# Hub.net
KiCad netlist of a schematic drawn in EAGLE
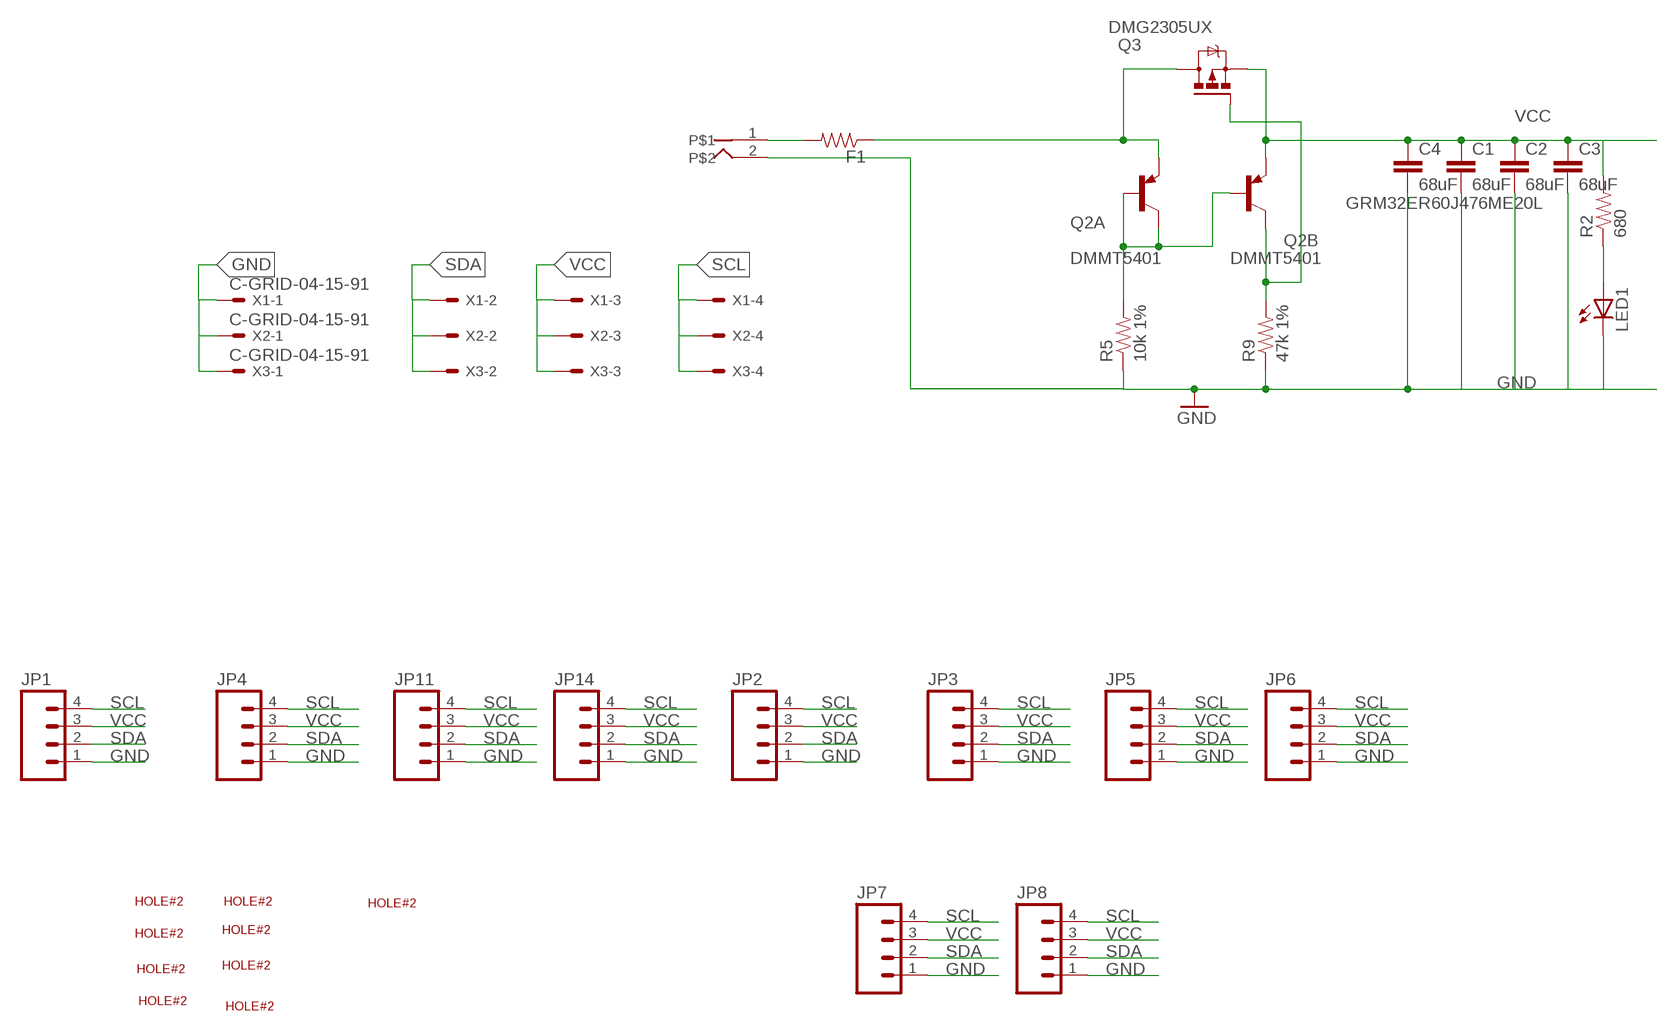
[diagram p0: schematic, sheet 1]

(export (version "E")
  (design (tool "Eeschema 10.0.6"))
  (components
    (comp (ref "C1")
      (value "68uF")
      (footprint "eagle-import:1210")
      (libsource (lib "eagle-import") (part "CAP1210"))
    )
    (comp (ref "C2")
      (value "68uF")
      (footprint "eagle-import:1210")
      (libsource (lib "eagle-import") (part "CAP1210"))
    )
    (comp (ref "C3")
      (value "68uF")
      (footprint "eagle-import:1210")
      (libsource (lib "eagle-import") (part "CAP1210"))
    )
    (comp (ref "C4")
      (value "68uF")
      (footprint "eagle-import:1210")
      (libsource (lib "eagle-import") (part "CAP1210"))
    )
    (comp (ref "F1")
      (value "RESISTOR0805-RES")
      (footprint "eagle-import:0805")
      (libsource (lib "eagle-import") (part "RESISTOR0805-RES"))
    )
    (comp (ref "JP1")
      (value "M04LOCK")
      (footprint "eagle-import:1X04_LOCK")
      (libsource (lib "eagle-import") (part "M04LOCK"))
    )
    (comp (ref "JP2")
      (value "M04LOCK")
      (footprint "eagle-import:1X04_LOCK")
      (libsource (lib "eagle-import") (part "M04LOCK"))
    )
    (comp (ref "JP3")
      (value "M04LOCK")
      (footprint "eagle-import:1X04_LOCK")
      (libsource (lib "eagle-import") (part "M04LOCK"))
    )
    (comp (ref "JP4")
      (value "M04LOCK")
      (footprint "eagle-import:1X04_LOCK")
      (libsource (lib "eagle-import") (part "M04LOCK"))
    )
    (comp (ref "JP5")
      (value "M04LOCK")
      (footprint "eagle-import:1X04_LOCK")
      (libsource (lib "eagle-import") (part "M04LOCK"))
    )
    (comp (ref "JP6")
      (value "M04LOCK")
      (footprint "eagle-import:1X04_LOCK")
      (libsource (lib "eagle-import") (part "M04LOCK"))
    )
    (comp (ref "JP7")
      (value "M04LOCK")
      (footprint "eagle-import:1X04_LOCK")
      (libsource (lib "eagle-import") (part "M04LOCK"))
    )
    (comp (ref "JP8")
      (value "M04LOCK")
      (footprint "eagle-import:1X04_LOCK")
      (libsource (lib "eagle-import") (part "M04LOCK"))
    )
    (comp (ref "JP11")
      (value "M04LOCK")
      (footprint "eagle-import:1X04_LOCK")
      (libsource (lib "eagle-import") (part "M04LOCK"))
    )
    (comp (ref "JP14")
      (value "M04LOCK")
      (footprint "eagle-import:1X04_LOCK")
      (libsource (lib "eagle-import") (part "M04LOCK"))
    )
    (comp (ref "LED1")
      (value "LEDCHIP-LED0805")
      (footprint "eagle-import:CHIP-LED0805")
      (libsource (lib "eagle-import") (part "LEDCHIP-LED0805"))
    )
    (comp (ref "Q2")
      (value "DMMT5401")
      (footprint "eagle-import:SOT-26")
      (libsource (lib "eagle-import") (part "TRANSISTOR-DUAL-PNP"))
    )
    (comp (ref "Q3")
      (value "DMG2305UX")
      (footprint "eagle-import:MICRO3")
      (libsource (lib "eagle-import") (part "IRLML5203"))
    )
    (comp (ref "R2")
      (value "680")
      (footprint "eagle-import:0805")
      (libsource (lib "eagle-import") (part "RESISTOR0805-RES"))
    )
    (comp (ref "R5")
      (value "10k 1%")
      (footprint "eagle-import:0805")
      (libsource (lib "eagle-import") (part "RESISTOR0805-RES"))
    )
    (comp (ref "R9")
      (value "47k 1%")
      (footprint "eagle-import:0805")
      (libsource (lib "eagle-import") (part "RESISTOR0805-RES"))
    )
    (comp (ref "U$1")
      (value "DC-JACKLOWPRO")
      (footprint "eagle-import:DC-POWER-JACK-LOWPRO")
      (libsource (lib "eagle-import") (part "DC-JACKLOWPRO"))
    )
    (comp (ref "U$6")
      (value "HOLE#2")
      (footprint "eagle-import:HOLE-#2")
      (libsource (lib "eagle-import") (part "HOLE#2"))
    )
    (comp (ref "U$7")
      (value "HOLE#2")
      (footprint "eagle-import:HOLE-#2")
      (libsource (lib "eagle-import") (part "HOLE#2"))
    )
    (comp (ref "U$8")
      (value "HOLE#2")
      (footprint "eagle-import:HOLE-#2")
      (libsource (lib "eagle-import") (part "HOLE#2"))
    )
    (comp (ref "U$9")
      (value "HOLE#2")
      (footprint "eagle-import:HOLE-#2")
      (libsource (lib "eagle-import") (part "HOLE#2"))
    )
    (comp (ref "U$10")
      (value "HOLE#2")
      (footprint "eagle-import:HOLE-#2")
      (libsource (lib "eagle-import") (part "HOLE#2"))
    )
    (comp (ref "U$11")
      (value "HOLE#2")
      (footprint "eagle-import:HOLE-#2")
      (libsource (lib "eagle-import") (part "HOLE#2"))
    )
    (comp (ref "U$12")
      (value "HOLE#2")
      (footprint "eagle-import:HOLE-#2")
      (libsource (lib "eagle-import") (part "HOLE#2"))
    )
    (comp (ref "U$13")
      (value "HOLE#2")
      (footprint "eagle-import:HOLE-#2")
      (libsource (lib "eagle-import") (part "HOLE#2"))
    )
    (comp (ref "U$14")
      (value "HOLE#2")
      (footprint "eagle-import:HOLE-#2")
      (libsource (lib "eagle-import") (part "HOLE#2"))
    )
    (comp (ref "X1")
      (value "C-GRID-04-15-91")
      (footprint "eagle-import:15-91-04")
      (libsource (lib "eagle-import") (part "C-GRID-04-15-91"))
    )
    (comp (ref "X2")
      (value "C-GRID-04-15-91")
      (footprint "eagle-import:15-91-04")
      (libsource (lib "eagle-import") (part "C-GRID-04-15-91"))
    )
    (comp (ref "X3")
      (value "C-GRID-04-15-91")
      (footprint "eagle-import:15-91-04")
      (libsource (lib "eagle-import") (part "C-GRID-04-15-91"))
    )
  )
  (nets
    (net (code "1") (name "GND") (class "Default")
      (node (ref "C1") (pin "2") (pinfunction "2_2") (pintype "passive"))
      (node (ref "C2") (pin "2") (pinfunction "2_2") (pintype "passive"))
      (node (ref "C3") (pin "2") (pinfunction "2_2") (pintype "passive"))
      (node (ref "C4") (pin "2") (pinfunction "2_2") (pintype "passive"))
      (node (ref "JP1") (pin "1") (pinfunction "1_1") (pintype "passive"))
      (node (ref "JP11") (pin "1") (pinfunction "1_1") (pintype "passive"))
      (node (ref "JP14") (pin "1") (pinfunction "1_1") (pintype "passive"))
      (node (ref "JP2") (pin "1") (pinfunction "1_1") (pintype "passive"))
      (node (ref "JP3") (pin "1") (pinfunction "1_1") (pintype "passive"))
      (node (ref "JP4") (pin "1") (pinfunction "1_1") (pintype "passive"))
      (node (ref "JP5") (pin "1") (pinfunction "1_1") (pintype "passive"))
      (node (ref "JP6") (pin "1") (pinfunction "1_1") (pintype "passive"))
      (node (ref "JP7") (pin "1") (pinfunction "1_1") (pintype "passive"))
      (node (ref "JP8") (pin "1") (pinfunction "1_1") (pintype "passive"))
      (node (ref "LED1") (pin "C") (pinfunction "C_C") (pintype "passive"))
      (node (ref "R5") (pin "1") (pinfunction "1_1") (pintype "passive"))
      (node (ref "R9") (pin "1") (pinfunction "1_1") (pintype "passive"))
      (node (ref "U$1") (pin "2") (pinfunction "P$2_2") (pintype "bidirectional"))
      (node (ref "X1") (pin "1") (pinfunction "S_1") (pintype "passive"))
      (node (ref "X2") (pin "1") (pinfunction "S_1") (pintype "passive"))
      (node (ref "X3") (pin "1") (pinfunction "S_1") (pintype "passive"))
    )
    (net (code "2") (name "Net-(LED1-PadA)") (class "Default")
      (node (ref "LED1") (pin "A") (pinfunction "A_A") (pintype "passive"))
      (node (ref "R2") (pin "1") (pinfunction "1_1") (pintype "passive"))
    )
    (net (code "3") (name "Net-(Q2A-B)") (class "Default")
      (node (ref "Q2") (pin "1") (pinfunction "C_1") (pintype "passive"))
      (node (ref "Q2") (pin "2") (pinfunction "B_2") (pintype "passive"))
      (node (ref "Q2") (pin "3") (pinfunction "B_3") (pintype "passive"))
      (node (ref "R5") (pin "2") (pinfunction "2_2") (pintype "passive"))
    )
    (net (code "4") (name "Net-(Q2A-E)") (class "Default")
      (node (ref "F1") (pin "1") (pinfunction "1_1") (pintype "passive"))
      (node (ref "Q2") (pin "6") (pinfunction "E_6") (pintype "passive"))
      (node (ref "Q3") (pin "3") (pinfunction "D_3") (pintype "passive"))
    )
    (net (code "5") (name "Net-(Q2B-C)") (class "Default")
      (node (ref "Q2") (pin "4") (pinfunction "C_4") (pintype "passive"))
      (node (ref "Q3") (pin "1") (pinfunction "G_1") (pintype "passive"))
      (node (ref "R9") (pin "2") (pinfunction "2_2") (pintype "passive"))
    )
    (net (code "6") (name "Net-(U$1-P$1)") (class "Default")
      (node (ref "F1") (pin "2") (pinfunction "2_2") (pintype "passive"))
      (node (ref "U$1") (pin "1") (pinfunction "P$1_1") (pintype "bidirectional"))
    )
    (net (code "7") (name "SCL") (class "Default")
      (node (ref "JP1") (pin "4") (pinfunction "4_4") (pintype "passive"))
      (node (ref "JP11") (pin "4") (pinfunction "4_4") (pintype "passive"))
      (node (ref "JP14") (pin "4") (pinfunction "4_4") (pintype "passive"))
      (node (ref "JP2") (pin "4") (pinfunction "4_4") (pintype "passive"))
      (node (ref "JP3") (pin "4") (pinfunction "4_4") (pintype "passive"))
      (node (ref "JP4") (pin "4") (pinfunction "4_4") (pintype "passive"))
      (node (ref "JP5") (pin "4") (pinfunction "4_4") (pintype "passive"))
      (node (ref "JP6") (pin "4") (pinfunction "4_4") (pintype "passive"))
      (node (ref "JP7") (pin "4") (pinfunction "4_4") (pintype "passive"))
      (node (ref "JP8") (pin "4") (pinfunction "4_4") (pintype "passive"))
      (node (ref "X1") (pin "4") (pinfunction "S_4") (pintype "passive"))
      (node (ref "X2") (pin "4") (pinfunction "S_4") (pintype "passive"))
      (node (ref "X3") (pin "4") (pinfunction "S_4") (pintype "passive"))
    )
    (net (code "8") (name "SDA") (class "Default")
      (node (ref "JP1") (pin "2") (pinfunction "2_2") (pintype "passive"))
      (node (ref "JP11") (pin "2") (pinfunction "2_2") (pintype "passive"))
      (node (ref "JP14") (pin "2") (pinfunction "2_2") (pintype "passive"))
      (node (ref "JP2") (pin "2") (pinfunction "2_2") (pintype "passive"))
      (node (ref "JP3") (pin "2") (pinfunction "2_2") (pintype "passive"))
      (node (ref "JP4") (pin "2") (pinfunction "2_2") (pintype "passive"))
      (node (ref "JP5") (pin "2") (pinfunction "2_2") (pintype "passive"))
      (node (ref "JP6") (pin "2") (pinfunction "2_2") (pintype "passive"))
      (node (ref "JP7") (pin "2") (pinfunction "2_2") (pintype "passive"))
      (node (ref "JP8") (pin "2") (pinfunction "2_2") (pintype "passive"))
      (node (ref "X1") (pin "2") (pinfunction "S_2") (pintype "passive"))
      (node (ref "X2") (pin "2") (pinfunction "S_2") (pintype "passive"))
      (node (ref "X3") (pin "2") (pinfunction "S_2") (pintype "passive"))
    )
    (net (code "9") (name "VCC") (class "Default")
      (node (ref "C1") (pin "1") (pinfunction "1_1") (pintype "passive"))
      (node (ref "C2") (pin "1") (pinfunction "1_1") (pintype "passive"))
      (node (ref "C3") (pin "1") (pinfunction "1_1") (pintype "passive"))
      (node (ref "C4") (pin "1") (pinfunction "1_1") (pintype "passive"))
      (node (ref "JP1") (pin "3") (pinfunction "3_3") (pintype "passive"))
      (node (ref "JP11") (pin "3") (pinfunction "3_3") (pintype "passive"))
      (node (ref "JP14") (pin "3") (pinfunction "3_3") (pintype "passive"))
      (node (ref "JP2") (pin "3") (pinfunction "3_3") (pintype "passive"))
      (node (ref "JP3") (pin "3") (pinfunction "3_3") (pintype "passive"))
      (node (ref "JP4") (pin "3") (pinfunction "3_3") (pintype "passive"))
      (node (ref "JP5") (pin "3") (pinfunction "3_3") (pintype "passive"))
      (node (ref "JP6") (pin "3") (pinfunction "3_3") (pintype "passive"))
      (node (ref "JP7") (pin "3") (pinfunction "3_3") (pintype "passive"))
      (node (ref "JP8") (pin "3") (pinfunction "3_3") (pintype "passive"))
      (node (ref "Q2") (pin "5") (pinfunction "E_5") (pintype "passive"))
      (node (ref "Q3") (pin "2") (pinfunction "S_2") (pintype "passive"))
      (node (ref "R2") (pin "2") (pinfunction "2_2") (pintype "passive"))
      (node (ref "X1") (pin "3") (pinfunction "S_3") (pintype "passive"))
      (node (ref "X2") (pin "3") (pinfunction "S_3") (pintype "passive"))
      (node (ref "X3") (pin "3") (pinfunction "S_3") (pintype "passive"))
    )
    (net (code "10") (name "unconnected-(U$6-HOLE-PadP$1)") (class "Default")
      (node (ref "U$6") (pin "P$1") (pinfunction "HOLE_P$1") (pintype "bidirectional"))
    )
    (net (code "11") (name "unconnected-(U$7-HOLE-PadP$1)") (class "Default")
      (node (ref "U$7") (pin "P$1") (pinfunction "HOLE_P$1") (pintype "bidirectional"))
    )
    (net (code "12") (name "unconnected-(U$8-HOLE-PadP$1)") (class "Default")
      (node (ref "U$8") (pin "P$1") (pinfunction "HOLE_P$1") (pintype "bidirectional"))
    )
    (net (code "13") (name "unconnected-(U$9-HOLE-PadP$1)") (class "Default")
      (node (ref "U$9") (pin "P$1") (pinfunction "HOLE_P$1") (pintype "bidirectional"))
    )
    (net (code "14") (name "unconnected-(U$10-HOLE-PadP$1)") (class "Default")
      (node (ref "U$10") (pin "P$1") (pinfunction "HOLE_P$1") (pintype "bidirectional"))
    )
    (net (code "15") (name "unconnected-(U$11-HOLE-PadP$1)") (class "Default")
      (node (ref "U$11") (pin "P$1") (pinfunction "HOLE_P$1") (pintype "bidirectional"))
    )
    (net (code "16") (name "unconnected-(U$12-HOLE-PadP$1)") (class "Default")
      (node (ref "U$12") (pin "P$1") (pinfunction "HOLE_P$1") (pintype "bidirectional"))
    )
    (net (code "17") (name "unconnected-(U$13-HOLE-PadP$1)") (class "Default")
      (node (ref "U$13") (pin "P$1") (pinfunction "HOLE_P$1") (pintype "bidirectional"))
    )
    (net (code "18") (name "unconnected-(U$14-HOLE-PadP$1)") (class "Default")
      (node (ref "U$14") (pin "P$1") (pinfunction "HOLE_P$1") (pintype "bidirectional"))
    )
  )
)
